# RX-FM-Radio-Circuit.net
KiCad netlist of a schematic drawn in EAGLE
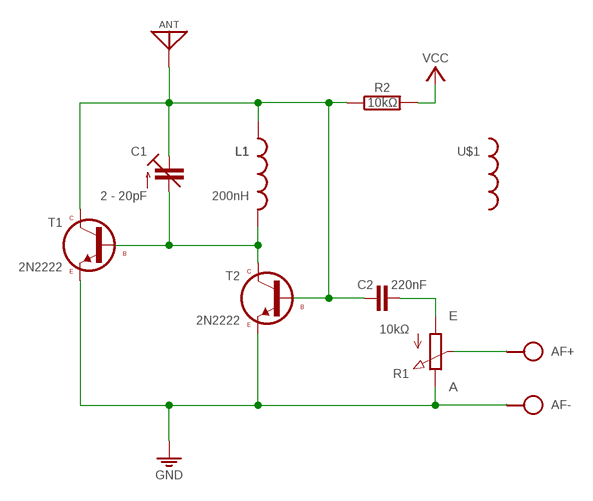
[diagram p0: schematic, sheet 1]

(export (version "E")
  (design (tool "Eeschema 10.0.6"))
  (components
    (comp (ref "AF")
      (value "SPAD+-+-")
      (footprint "eagle-import:SPAD+-")
      (libsource (lib "eagle-import") (part "SPAD+-+-"))
    )
    (comp (ref "ANT")
      (value "ANT")
      (footprint "eagle-import:SPAD")
      (libsource (lib "eagle-import") (part "ANT"))
    )
    (comp (ref "BAT")
      (value "VCC_GNDL")
      (footprint "eagle-import:SPAD-+")
      (libsource (lib "eagle-import") (part "VCC_GNDL"))
    )
    (comp (ref "C1")
      (value "2 - 20pF")
      (footprint "eagle-import:TRIM-2222-808")
      (libsource (lib "eagle-import") (part "C-TR-PH201272222-808-2PINB"))
    )
    (comp (ref "C2")
      (value "220nF")
      (footprint "eagle-import:C050-020X044")
      (libsource (lib "eagle-import") (part "C-H050-020X044"))
    )
    (comp (ref "L1")
      (value "200nH")
      (footprint "eagle-import:L-04_7-V")
      (libsource (lib "eagle-import") (part "L04/7-V"))
    )
    (comp (ref "R1")
      (value "10kΩ")
      (footprint "eagle-import:POT")
      (libsource (lib "eagle-import") (part "POT"))
    )
    (comp (ref "R2")
      (value "10kΩ")
      (footprint "eagle-import:0204_10")
      (libsource (lib "eagle-import") (part "R-H0204/10"))
    )
    (comp (ref "T1")
      (value "2N2222")
      (footprint "eagle-import:TO92-EBC")
      (libsource (lib "eagle-import") (part "2N2222"))
    )
    (comp (ref "T2")
      (value "2N2222")
      (footprint "eagle-import:TO92-EBC")
      (libsource (lib "eagle-import") (part "2N2222"))
    )
    (comp (ref "U$1")
      (value "L-ALT-TEST")
      (footprint "eagle-import:TEST")
      (libsource (lib "eagle-import") (part "L-ALT-TEST"))
    )
  )
  (nets
    (net (code "1") (name "Net-(AFA-P$1)") (class "Default")
      (node (ref "AF") (pin "2") (pinfunction "P$1_2") (pintype "passive"))
      (node (ref "R1") (pin "S") (pinfunction "S_S") (pintype "passive"))
    )
    (net (code "2") (name "Net-(AFB-P$1)") (class "Default")
      (node (ref "AF") (pin "1") (pinfunction "P$1_1") (pintype "passive"))
      (node (ref "BAT") (pin "1") (pinfunction "GND_1") (pintype "power_in"))
      (node (ref "R1") (pin "E") (pinfunction "E_E") (pintype "passive"))
      (node (ref "T1") (pin "E") (pinfunction "E_E") (pintype "passive"))
      (node (ref "T2") (pin "E") (pinfunction "E_E") (pintype "passive"))
    )
    (net (code "3") (name "Net-(BATA-VCC)") (class "Default")
      (node (ref "BAT") (pin "2") (pinfunction "VCC_2") (pintype "power_in"))
      (node (ref "R2") (pin "2") (pinfunction "2_2") (pintype "passive"))
    )
    (net (code "4") (name "Net-(C1-A)") (class "Default")
      (node (ref "C1") (pin "2") (pinfunction "A_2") (pintype "passive"))
      (node (ref "L1") (pin "2") (pinfunction "2_2") (pintype "passive"))
      (node (ref "T1") (pin "B") (pinfunction "B_B") (pintype "passive"))
      (node (ref "T2") (pin "C") (pinfunction "C_C") (pintype "passive"))
    )
    (net (code "5") (name "Net-(C1-E)") (class "Default")
      (node (ref "ANT") (pin "1") (pinfunction "1_1") (pintype "output"))
      (node (ref "C1") (pin "3") (pinfunction "E_3") (pintype "passive"))
      (node (ref "C2") (pin "1") (pinfunction "1_1") (pintype "passive"))
      (node (ref "L1") (pin "1") (pinfunction "1_1") (pintype "passive"))
      (node (ref "R2") (pin "1") (pinfunction "1_1") (pintype "passive"))
      (node (ref "T1") (pin "C") (pinfunction "C_C") (pintype "passive"))
      (node (ref "T2") (pin "B") (pinfunction "B_B") (pintype "passive"))
    )
    (net (code "6") (name "Net-(C2-Pad2)") (class "Default")
      (node (ref "C2") (pin "2") (pinfunction "2_2") (pintype "passive"))
      (node (ref "R1") (pin "A") (pinfunction "A_A") (pintype "passive"))
    )
    (net (code "7") (name "unconnected-(U$1-Pad1)") (class "Default")
      (node (ref "U$1") (pin "1") (pinfunction "1_1") (pintype "passive"))
    )
    (net (code "8") (name "unconnected-(U$1-Pad2)") (class "Default")
      (node (ref "U$1") (pin "2") (pinfunction "2_2") (pintype "passive"))
    )
  )
)
